# smartport_inverter.net
KiCad netlist of a schematic drawn in Altium Designer
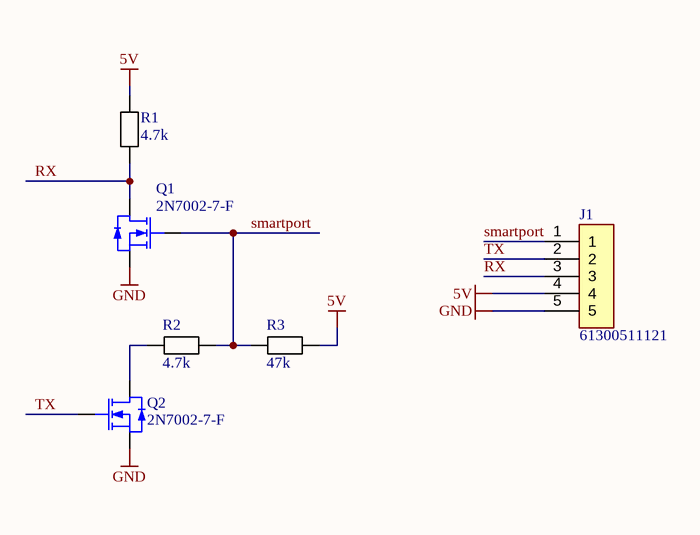
[diagram p0: smartport_inverter.SchDoc]

(export (version "E")
  (design (tool "Eeschema 10.0.6"))
  (components
    (comp (ref "J1")
      (value "61300511121")
      (footprint "61300511121")
      (description "Headers & Wire Housings WR-PHD 2.54mm Hdr 5P Single Str Gold")
      (fields (field (name "MANUFACTURER") "Wurth Elektronik"))
      (libsource (lib "EnergyMeter") (part "61300511121"))
    )
    (comp (ref "Q1")
      (value "2N7002-7-F")
      (footprint "SOT23-3N")
      (description "MOSFET N-CH 60V 200MA SOT23-3")
      (fields (field (name "MANUFACTURER") "Diodes Incorporated"))
      (libsource (lib "EnergyMeter") (part "2N7002-7-F"))
    )
    (comp (ref "Q2")
      (value "2N7002-7-F")
      (footprint "SOT23-3N")
      (description "MOSFET N-CH 60V 200MA SOT23-3")
      (fields (field (name "MANUFACTURER") "Diodes Incorporated"))
      (libsource (lib "EnergyMeter") (part "2N7002-7-F"))
    )
    (comp (ref "R1")
      (value "4.7k")
      (footprint "R0603")
      (description "Resistor 4.7k 0603 +-1% 0.1")
      (fields (field (name "PART NUMBER") "RES_YAG_RC0603FR-074K7L") (field (name "MANUFACTURER") "Yageo"))
      (libsource (lib "Res_Yag_0603_1%$") (part "RES_YAG_RC0603FR-074K7L"))
    )
    (comp (ref "R2")
      (value "4.7k")
      (footprint "R0603")
      (description "Resistor 4.7k 0603 +-1% 0.1")
      (fields (field (name "PART NUMBER") "RES_YAG_RC0603FR-074K7L") (field (name "MANUFACTURER") "Yageo"))
      (libsource (lib "Res_Yag_0603_1%$") (part "RES_YAG_RC0603FR-074K7L"))
    )
    (comp (ref "R3")
      (value "47k")
      (footprint "R0603")
      (description "Resistor 47k 0603 +-1% 0.1")
      (fields (field (name "PART NUMBER") "RES_YAG_RC0603FR-0747KL") (field (name "MANUFACTURER") "Yageo"))
      (libsource (lib "Res_Yag_0603_1%$") (part "RES_YAG_RC0603FR-0747KL"))
    )
  )
  (nets
    (net (code "1") (name "/RX") (class "Default")
      (node (ref "J1") (pin "3") (pinfunction "3_3") (pintype "passive"))
      (node (ref "Q1") (pin "3") (pinfunction "D_3") (pintype "passive"))
      (node (ref "R1") (pin "1") (pinfunction "1_1") (pintype "passive"))
    )
    (net (code "2") (name "/TX") (class "Default")
      (node (ref "J1") (pin "2") (pinfunction "2_2") (pintype "passive"))
      (node (ref "Q2") (pin "1") (pinfunction "G_1") (pintype "passive"))
    )
    (net (code "3") (name "/smartport") (class "Default")
      (node (ref "J1") (pin "1") (pinfunction "1_1") (pintype "passive"))
      (node (ref "Q1") (pin "1") (pinfunction "G_1") (pintype "passive"))
      (node (ref "R2") (pin "1") (pinfunction "1_1") (pintype "passive"))
      (node (ref "R3") (pin "2") (pinfunction "2_2") (pintype "passive"))
    )
    (net (code "4") (name "5V") (class "Default")
      (node (ref "J1") (pin "4") (pinfunction "4_4") (pintype "passive"))
      (node (ref "R1") (pin "2") (pinfunction "2_2") (pintype "passive"))
      (node (ref "R3") (pin "1") (pinfunction "1_1") (pintype "passive"))
    )
    (net (code "5") (name "GND") (class "Default")
      (node (ref "J1") (pin "5") (pinfunction "5_5") (pintype "passive"))
      (node (ref "Q1") (pin "2") (pinfunction "S_2") (pintype "passive"))
      (node (ref "Q2") (pin "2") (pinfunction "S_2") (pintype "passive"))
    )
    (net (code "6") (name "Net-(Q2-D)") (class "Default")
      (node (ref "Q2") (pin "3") (pinfunction "D_3") (pintype "passive"))
      (node (ref "R2") (pin "2") (pinfunction "2_2") (pintype "passive"))
    )
  )
)
